# NEW5V.net
KiCad netlist of a schematic drawn in EAGLE
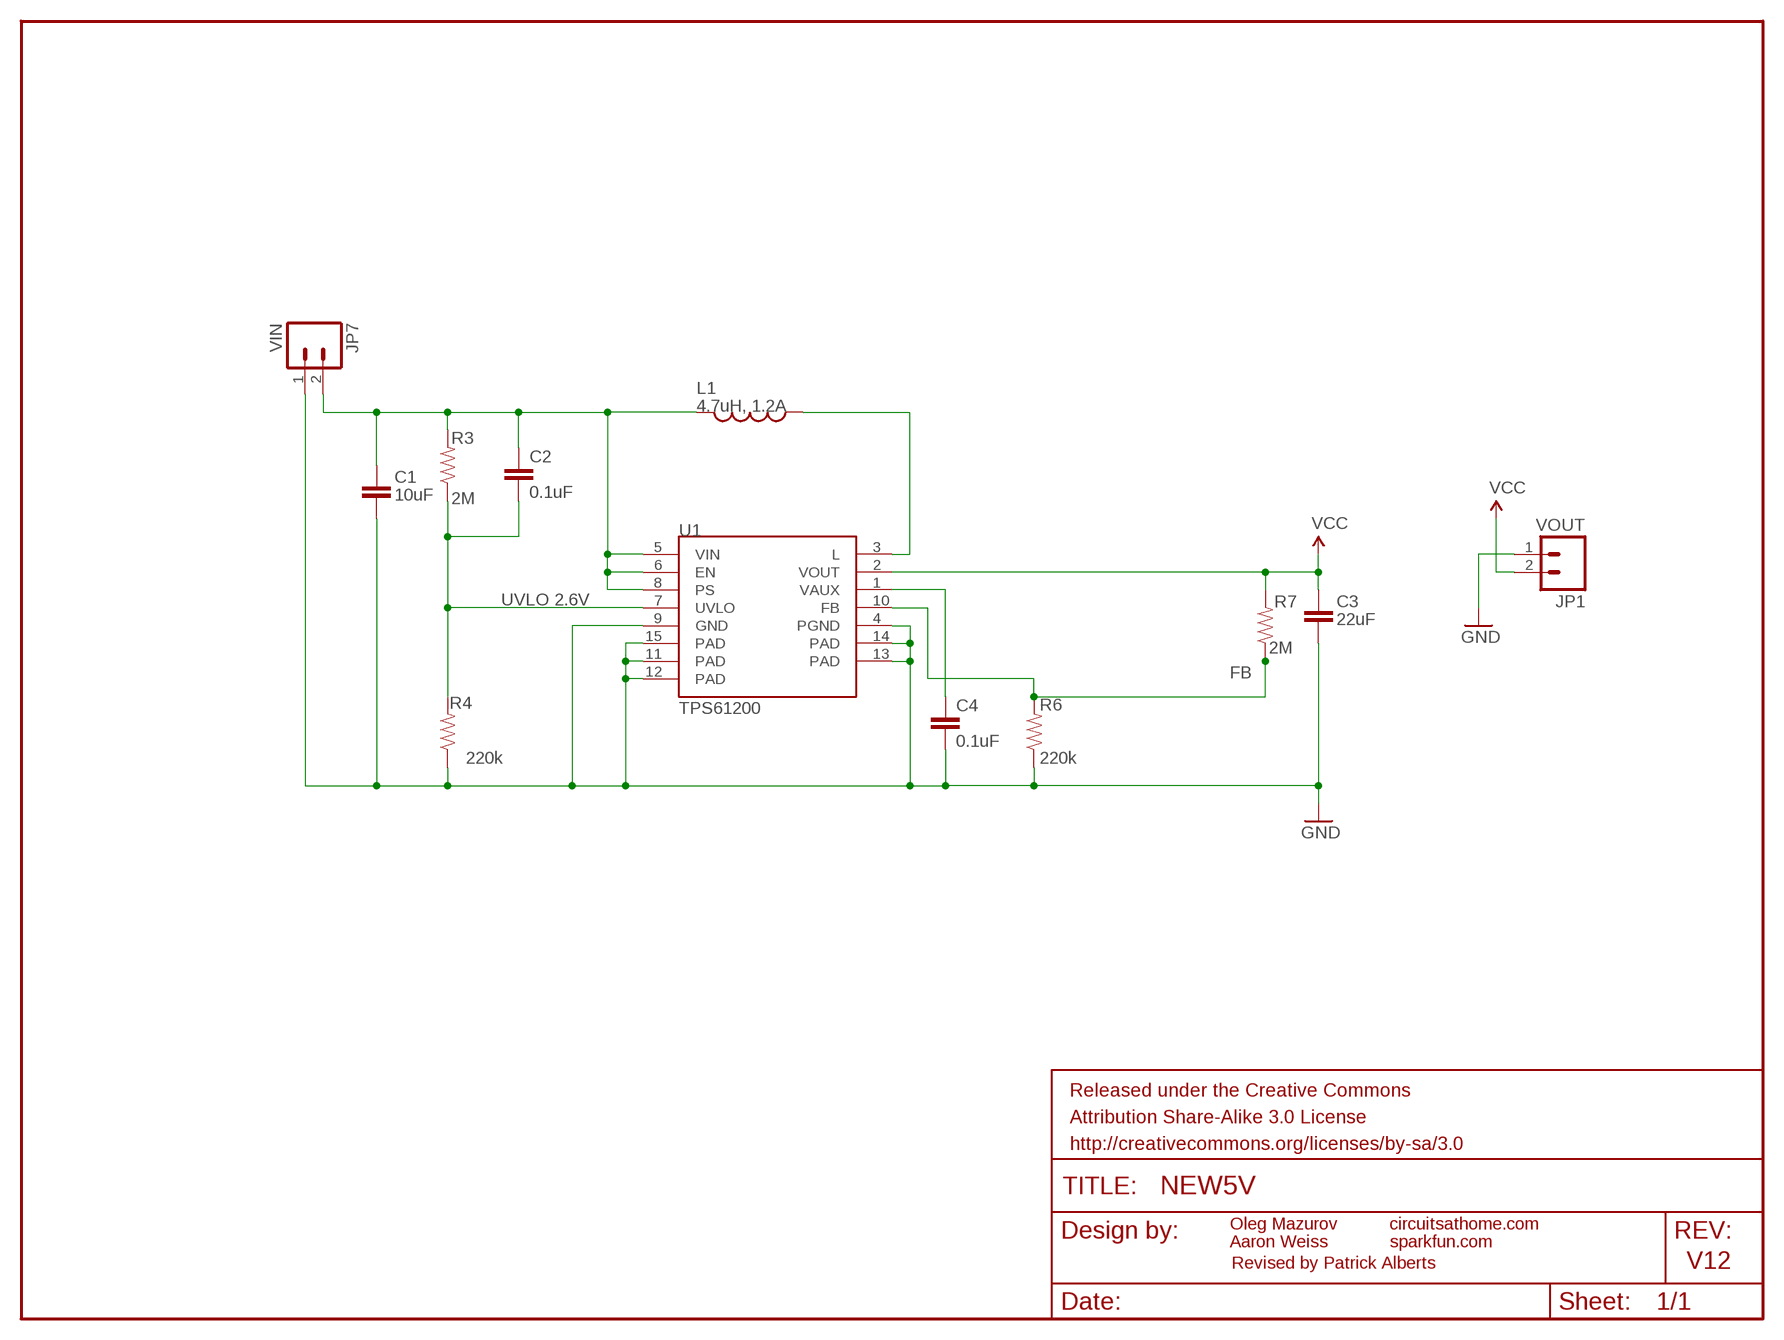
[diagram p0: schematic, sheet 1]

(export (version "E")
  (design (tool "Eeschema 10.0.6"))
  (components
    (comp (ref "C1")
      (value "10uF")
      (footprint "eagle-import:1206")
      (libsource (lib "eagle-import") (part "CAP1206"))
    )
    (comp (ref "C2")
      (value "0.1uF")
      (footprint "eagle-import:0603-CAP")
      (libsource (lib "eagle-import") (part "CAP0603-CAP"))
    )
    (comp (ref "C3")
      (value "22uF")
      (footprint "eagle-import:0805")
      (libsource (lib "eagle-import") (part "CAP0805"))
    )
    (comp (ref "C4")
      (value "0.1uF")
      (footprint "eagle-import:0603-CAP")
      (libsource (lib "eagle-import") (part "CAP0603-CAP"))
    )
    (comp (ref "FRAME1")
      (value "FRAME-LETTER")
      (footprint "eagle-import:CREATIVE_COMMONS")
      (libsource (lib "eagle-import") (part "FRAME-LETTER"))
    )
    (comp (ref "JP1")
      (value "VOUT")
      (footprint "eagle-import:1X02")
      (libsource (lib "eagle-import") (part "M02PTH"))
    )
    (comp (ref "JP7")
      (value "VIN")
      (footprint "eagle-import:1X02")
      (libsource (lib "eagle-import") (part "M02PTH"))
    )
    (comp (ref "L1")
      (value "4.7uH, 1.2A")
      (footprint "eagle-import:CDRH2D09")
      (libsource (lib "eagle-import") (part "INDUCTOR."))
    )
    (comp (ref "R3")
      (value "2M")
      (footprint "eagle-import:0603-RES")
      (libsource (lib "eagle-import") (part "RESISTOR0603-RES"))
    )
    (comp (ref "R4")
      (value "220k")
      (footprint "eagle-import:0603-RES")
      (libsource (lib "eagle-import") (part "RESISTOR0603-RES"))
    )
    (comp (ref "R6")
      (value "220k")
      (footprint "eagle-import:0603-RES")
      (libsource (lib "eagle-import") (part "RESISTOR0603-RES"))
    )
    (comp (ref "R7")
      (value "2M")
      (footprint "eagle-import:0603-RES")
      (libsource (lib "eagle-import") (part "RESISTOR0603-RES"))
    )
    (comp (ref "U1")
      (value "TPS61200")
      (footprint "eagle-import:QFN-10_PAD")
      (libsource (lib "eagle-import") (part "TPS61200"))
    )
  )
  (nets
    (net (code "1") (name "/FB") (class "Default")
      (node (ref "R6") (pin "2") (pinfunction "2_2") (pintype "passive"))
      (node (ref "R7") (pin "1") (pinfunction "1_1") (pintype "passive"))
      (node (ref "U1") (pin "10") (pinfunction "FB_10") (pintype "passive"))
    )
    (net (code "2") (name "GND") (class "Default")
      (node (ref "C1") (pin "2") (pinfunction "2_2") (pintype "passive"))
      (node (ref "C3") (pin "2") (pinfunction "2_2") (pintype "passive"))
      (node (ref "C4") (pin "2") (pinfunction "2_2") (pintype "passive"))
      (node (ref "JP1") (pin "1") (pinfunction "1_1") (pintype "passive"))
      (node (ref "JP7") (pin "1") (pinfunction "1_1") (pintype "passive"))
      (node (ref "R4") (pin "1") (pinfunction "1_1") (pintype "passive"))
      (node (ref "R6") (pin "1") (pinfunction "1_1") (pintype "passive"))
      (node (ref "U1") (pin "11") (pinfunction "PAD_11") (pintype "power_in"))
      (node (ref "U1") (pin "12") (pinfunction "PAD_12") (pintype "power_in"))
      (node (ref "U1") (pin "13") (pinfunction "PAD_13") (pintype "power_in"))
      (node (ref "U1") (pin "14") (pinfunction "PAD_14") (pintype "power_in"))
      (node (ref "U1") (pin "15") (pinfunction "PAD_15") (pintype "power_in"))
      (node (ref "U1") (pin "4") (pinfunction "PGND_4") (pintype "power_in"))
      (node (ref "U1") (pin "9") (pinfunction "GND_9") (pintype "power_in"))
    )
    (net (code "3") (name "Net-(L1-1)") (class "Default")
      (node (ref "L1") (pin "P$1") (pinfunction "1_P$1") (pintype "passive"))
      (node (ref "U1") (pin "3") (pinfunction "L_3") (pintype "passive"))
    )
    (net (code "4") (name "Net-(L1-2)") (class "Default")
      (node (ref "C1") (pin "1") (pinfunction "1_1") (pintype "passive"))
      (node (ref "C2") (pin "1") (pinfunction "1_1") (pintype "passive"))
      (node (ref "JP7") (pin "2") (pinfunction "2_2") (pintype "passive"))
      (node (ref "L1") (pin "P$2") (pinfunction "2_P$2") (pintype "passive"))
      (node (ref "R3") (pin "2") (pinfunction "2_2") (pintype "passive"))
      (node (ref "U1") (pin "5") (pinfunction "VIN_5") (pintype "power_in"))
      (node (ref "U1") (pin "6") (pinfunction "EN_6") (pintype "input"))
      (node (ref "U1") (pin "8") (pinfunction "PS_8") (pintype "input"))
    )
    (net (code "5") (name "Net-(U1-UVLO)") (class "Default")
      (node (ref "C2") (pin "2") (pinfunction "2_2") (pintype "passive"))
      (node (ref "R3") (pin "1") (pinfunction "1_1") (pintype "passive"))
      (node (ref "R4") (pin "2") (pinfunction "2_2") (pintype "passive"))
      (node (ref "U1") (pin "7") (pinfunction "UVLO_7") (pintype "passive"))
    )
    (net (code "6") (name "Net-(U1-VAUX)") (class "Default")
      (node (ref "C4") (pin "1") (pinfunction "1_1") (pintype "passive"))
      (node (ref "U1") (pin "1") (pinfunction "VAUX_1") (pintype "passive"))
    )
    (net (code "7") (name "VCC") (class "Default")
      (node (ref "C3") (pin "1") (pinfunction "1_1") (pintype "passive"))
      (node (ref "JP1") (pin "2") (pinfunction "2_2") (pintype "passive"))
      (node (ref "R7") (pin "2") (pinfunction "2_2") (pintype "passive"))
      (node (ref "U1") (pin "2") (pinfunction "VOUT_2") (pintype "passive"))
    )
  )
)
